# FeatherGPS6.net
KiCad netlist of a schematic drawn in EAGLE
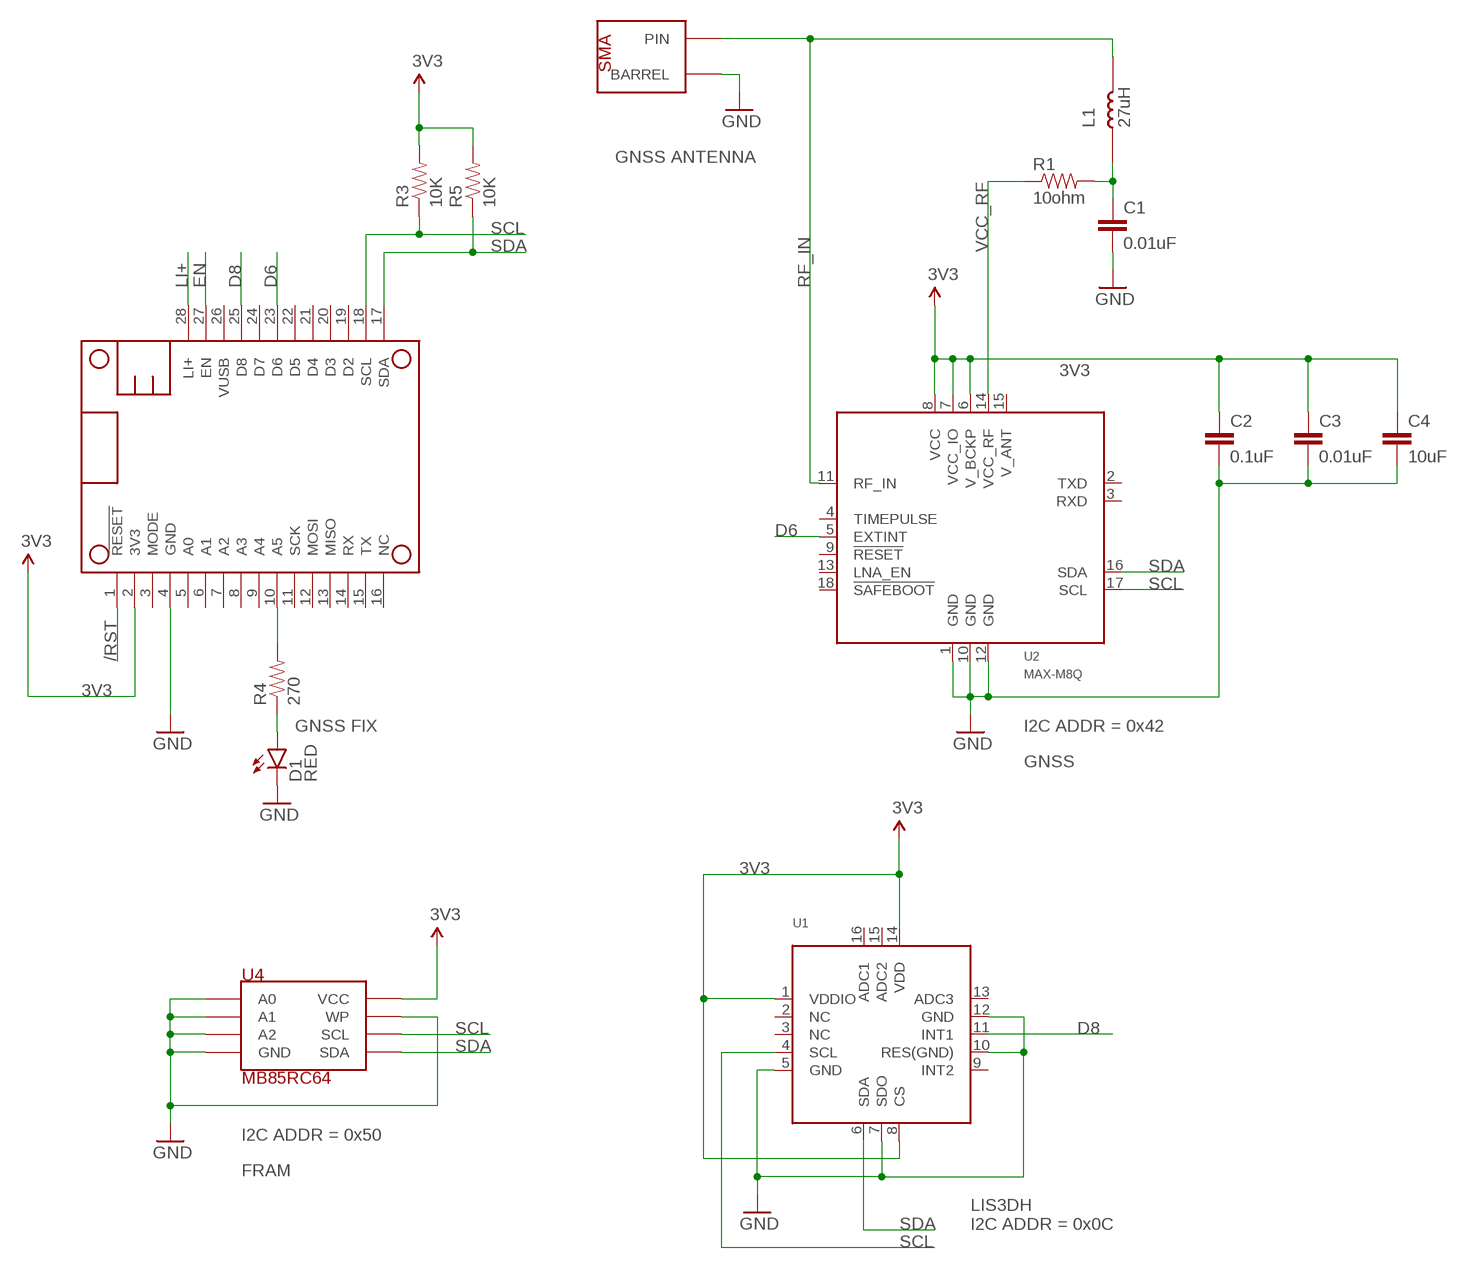
[diagram p0: schematic, sheet 1]

(export (version "E")
  (design (tool "Eeschema 10.0.6"))
  (components
    (comp (ref "C1")
      (value "0.01uF")
      (footprint "eagle-import:0603-CAP")
      (libsource (lib "eagle-import") (part "CAP-0.01UF-0603"))
    )
    (comp (ref "C2")
      (value "0.1uF")
      (footprint "eagle-import:0603-CAP")
      (libsource (lib "eagle-import") (part "CAP-0.1UF-0603"))
    )
    (comp (ref "C3")
      (value "0.01uF")
      (footprint "eagle-import:0603-CAP")
      (libsource (lib "eagle-import") (part "CAP-0.01UF-0603"))
    )
    (comp (ref "C4")
      (value "10uF")
      (footprint "eagle-import:0603-CAP")
      (libsource (lib "eagle-import") (part "CAP-10UF-0603"))
    )
    (comp (ref "D1")
      (value "RED")
      (footprint "eagle-import:LED-0603")
      (libsource (lib "eagle-import") (part "LED-RED"))
    )
    (comp (ref "J1")
      (value "SMA")
      (footprint "eagle-import:CONN-SMA")
      (libsource (lib "eagle-import") (part "CONN-SMA"))
    )
    (comp (ref "L1")
      (value "27uH")
      (footprint "eagle-import:0805")
      (libsource (lib "eagle-import") (part "INDUCTOR-27UH"))
    )
    (comp (ref "MS1")
      (value "FEATHERWING_NODIM")
      (footprint "eagle-import:FEATHERWING_NODIM")
      (libsource (lib "eagle-import") (part "FEATHERWING_NODIM"))
    )
    (comp (ref "R1")
      (value "10ohm")
      (footprint "eagle-import:0603-RES")
      (libsource (lib "eagle-import") (part "RES-10-06030603"))
    )
    (comp (ref "R3")
      (value "10K")
      (footprint "eagle-import:0603-RES")
      (libsource (lib "eagle-import") (part "RES-10K-06030603"))
    )
    (comp (ref "R4")
      (value "270")
      (footprint "eagle-import:0603-RES")
      (libsource (lib "eagle-import") (part "RES-270-0603.DEV"))
    )
    (comp (ref "R5")
      (value "10K")
      (footprint "eagle-import:0603-RES")
      (libsource (lib "eagle-import") (part "RES-10K-06030603"))
    )
    (comp (ref "U1")
      (value "LIS3DHTR")
      (footprint "eagle-import:MICROBUILDER_LGA16_3X3MM")
      (libsource (lib "eagle-import") (part "LIS3DHTR"))
    )
    (comp (ref "U2")
      (value "MAX-M8Q")
      (footprint "eagle-import:U-BLOX_MAX-M8")
      (libsource (lib "eagle-import") (part "U-BLOX_MAX-M8"))
    )
    (comp (ref "U4")
      (value "MB85RC64")
      (footprint "eagle-import:8-SOIC-MAXIM")
      (libsource (lib "eagle-import") (part "MB85RC64-FRAM"))
    )
  )
  (nets
    (net (code "1") (name "/D6") (class "Default")
      (node (ref "MS1") (pin "23") (pinfunction "D6_23") (pintype "bidirectional"))
      (node (ref "U2") (pin "5") (pinfunction "EXTINT_5") (pintype "bidirectional"))
    )
    (net (code "2") (name "/D8") (class "Default")
      (node (ref "MS1") (pin "25") (pinfunction "D8_25") (pintype "bidirectional"))
      (node (ref "U1") (pin "11") (pinfunction "INT1_11") (pintype "output"))
    )
    (net (code "3") (name "/EN") (class "Default")
      (node (ref "MS1") (pin "27") (pinfunction "EN_27") (pintype "passive"))
    )
    (net (code "4") (name "/LI+") (class "Default")
      (node (ref "MS1") (pin "28") (pinfunction "LI+_28") (pintype "power_in"))
    )
    (net (code "5") (name "/RF_IN") (class "Default")
      (node (ref "J1") (pin "PIN") (pinfunction "PIN_PIN") (pintype "passive"))
      (node (ref "L1") (pin "2") (pinfunction "P$2_2") (pintype "passive"))
      (node (ref "U2") (pin "11") (pinfunction "RF_IN_11") (pintype "bidirectional"))
    )
    (net (code "6") (name "/SCL") (class "Default")
      (node (ref "MS1") (pin "18") (pinfunction "SCL_18") (pintype "bidirectional"))
      (node (ref "R3") (pin "1") (pinfunction "1_1") (pintype "passive"))
      (node (ref "U1") (pin "4") (pinfunction "SCL_4") (pintype "bidirectional"))
      (node (ref "U2") (pin "17") (pinfunction "SCL_17") (pintype "bidirectional"))
      (node (ref "U4") (pin "6") (pinfunction "SCL_6") (pintype "input"))
    )
    (net (code "7") (name "/SDA") (class "Default")
      (node (ref "MS1") (pin "17") (pinfunction "SDA_17") (pintype "bidirectional"))
      (node (ref "R5") (pin "1") (pinfunction "1_1") (pintype "passive"))
      (node (ref "U1") (pin "6") (pinfunction "SDA_6") (pintype "bidirectional"))
      (node (ref "U2") (pin "16") (pinfunction "SDA_16") (pintype "bidirectional"))
      (node (ref "U4") (pin "5") (pinfunction "SDA_5") (pintype "bidirectional"))
    )
    (net (code "8") (name "/VCC_RF") (class "Default")
      (node (ref "R1") (pin "1") (pinfunction "1_1") (pintype "passive"))
      (node (ref "U2") (pin "14") (pinfunction "VCC_RF_14") (pintype "bidirectional"))
    )
    (net (code "9") (name "/VUSB") (class "Default")
      (node (ref "MS1") (pin "26") (pinfunction "VUSB_26") (pintype "power_in"))
    )
    (net (code "10") (name "/{slash}RST") (class "Default")
      (node (ref "MS1") (pin "1") (pinfunction "~{RESET}_1") (pintype "input"))
    )
    (net (code "11") (name "3V3") (class "Default")
      (node (ref "C2") (pin "1") (pinfunction "1_1") (pintype "passive"))
      (node (ref "C3") (pin "1") (pinfunction "1_1") (pintype "passive"))
      (node (ref "C4") (pin "1") (pinfunction "1_1") (pintype "passive"))
      (node (ref "MS1") (pin "2") (pinfunction "3V3_2") (pintype "power_in"))
      (node (ref "R3") (pin "2") (pinfunction "2_2") (pintype "passive"))
      (node (ref "R5") (pin "2") (pinfunction "2_2") (pintype "passive"))
      (node (ref "U1") (pin "1") (pinfunction "VDDIO_1") (pintype "power_in"))
      (node (ref "U1") (pin "14") (pinfunction "VDD_14") (pintype "power_in"))
      (node (ref "U1") (pin "8") (pinfunction "CS_8") (pintype "input"))
      (node (ref "U2") (pin "6") (pinfunction "V_BCKP_6") (pintype "bidirectional"))
      (node (ref "U2") (pin "7") (pinfunction "VCC_IO_7") (pintype "bidirectional"))
      (node (ref "U2") (pin "8") (pinfunction "VCC_8") (pintype "bidirectional"))
      (node (ref "U4") (pin "8") (pinfunction "VCC_8") (pintype "power_in"))
    )
    (net (code "12") (name "GND") (class "Default")
      (node (ref "C1") (pin "2") (pinfunction "2_2") (pintype "passive"))
      (node (ref "C2") (pin "2") (pinfunction "2_2") (pintype "passive"))
      (node (ref "C3") (pin "2") (pinfunction "2_2") (pintype "passive"))
      (node (ref "C4") (pin "2") (pinfunction "2_2") (pintype "passive"))
      (node (ref "D1") (pin "C") (pinfunction "C_C") (pintype "passive"))
      (node (ref "J1") (pin "2") (pinfunction "BARREL_2") (pintype "passive"))
      (node (ref "J1") (pin "3") (pinfunction "BARREL_3") (pintype "passive"))
      (node (ref "J1") (pin "4") (pinfunction "BARREL_4") (pintype "passive"))
      (node (ref "J1") (pin "5") (pinfunction "BARREL_5") (pintype "passive"))
      (node (ref "MS1") (pin "4") (pinfunction "GND_4") (pintype "power_in"))
      (node (ref "U1") (pin "10") (pinfunction "RES(GND)_10") (pintype "bidirectional"))
      (node (ref "U1") (pin "12") (pinfunction "GND_12") (pintype "power_in"))
      (node (ref "U1") (pin "5") (pinfunction "GND_5") (pintype "power_in"))
      (node (ref "U1") (pin "7") (pinfunction "SDO_7") (pintype "bidirectional"))
      (node (ref "U2") (pin "1") (pinfunction "GND_1") (pintype "bidirectional"))
      (node (ref "U2") (pin "10") (pinfunction "GND_10") (pintype "bidirectional"))
      (node (ref "U2") (pin "12") (pinfunction "GND_12") (pintype "bidirectional"))
      (node (ref "U4") (pin "1") (pinfunction "A0_1") (pintype "input"))
      (node (ref "U4") (pin "2") (pinfunction "A1_2") (pintype "input"))
      (node (ref "U4") (pin "3") (pinfunction "A2_3") (pintype "input"))
      (node (ref "U4") (pin "4") (pinfunction "GND_4") (pintype "passive"))
      (node (ref "U4") (pin "7") (pinfunction "WP_7") (pintype "input"))
    )
    (net (code "13") (name "Net-(D1-PadA)") (class "Default")
      (node (ref "D1") (pin "A") (pinfunction "A_A") (pintype "passive"))
      (node (ref "R4") (pin "1") (pinfunction "1_1") (pintype "passive"))
    )
    (net (code "14") (name "Net-(L1-P$1)") (class "Default")
      (node (ref "C1") (pin "1") (pinfunction "1_1") (pintype "passive"))
      (node (ref "L1") (pin "1") (pinfunction "P$1_1") (pintype "passive"))
      (node (ref "R1") (pin "2") (pinfunction "2_2") (pintype "passive"))
    )
    (net (code "15") (name "Net-(MS1-A5)") (class "Default")
      (node (ref "MS1") (pin "10") (pinfunction "A5_10") (pintype "bidirectional"))
      (node (ref "R4") (pin "2") (pinfunction "2_2") (pintype "passive"))
    )
    (net (code "16") (name "unconnected-(MS1-A0-Pad5)") (class "Default")
      (node (ref "MS1") (pin "5") (pinfunction "A0_5") (pintype "bidirectional"))
    )
    (net (code "17") (name "unconnected-(MS1-A1-Pad6)") (class "Default")
      (node (ref "MS1") (pin "6") (pinfunction "A1_6") (pintype "bidirectional"))
    )
    (net (code "18") (name "unconnected-(MS1-A2-Pad7)") (class "Default")
      (node (ref "MS1") (pin "7") (pinfunction "A2_7") (pintype "bidirectional"))
    )
    (net (code "19") (name "unconnected-(MS1-A3-Pad8)") (class "Default")
      (node (ref "MS1") (pin "8") (pinfunction "A3_8") (pintype "bidirectional"))
    )
    (net (code "20") (name "unconnected-(MS1-A4-Pad9)") (class "Default")
      (node (ref "MS1") (pin "9") (pinfunction "A4_9") (pintype "bidirectional"))
    )
    (net (code "21") (name "unconnected-(MS1-D2-Pad19)") (class "Default")
      (node (ref "MS1") (pin "19") (pinfunction "D2_19") (pintype "bidirectional"))
    )
    (net (code "22") (name "unconnected-(MS1-D3-Pad20)") (class "Default")
      (node (ref "MS1") (pin "20") (pinfunction "D3_20") (pintype "bidirectional"))
    )
    (net (code "23") (name "unconnected-(MS1-D4-Pad21)") (class "Default")
      (node (ref "MS1") (pin "21") (pinfunction "D4_21") (pintype "bidirectional"))
    )
    (net (code "24") (name "unconnected-(MS1-D5-Pad22)") (class "Default")
      (node (ref "MS1") (pin "22") (pinfunction "D5_22") (pintype "bidirectional"))
    )
    (net (code "25") (name "unconnected-(MS1-D7-Pad24)") (class "Default")
      (node (ref "MS1") (pin "24") (pinfunction "D7_24") (pintype "bidirectional"))
    )
    (net (code "26") (name "unconnected-(MS1-MISO-Pad13)") (class "Default")
      (node (ref "MS1") (pin "13") (pinfunction "MISO_13") (pintype "bidirectional"))
    )
    (net (code "27") (name "unconnected-(MS1-MODE-Pad3)") (class "Default")
      (node (ref "MS1") (pin "3") (pinfunction "MODE_3") (pintype "passive"))
    )
    (net (code "28") (name "unconnected-(MS1-MOSI-Pad12)") (class "Default")
      (node (ref "MS1") (pin "12") (pinfunction "MOSI_12") (pintype "bidirectional"))
    )
    (net (code "29") (name "unconnected-(MS1-NC-Pad16)") (class "Default")
      (node (ref "MS1") (pin "16") (pinfunction "NC_16") (pintype "passive"))
    )
    (net (code "30") (name "unconnected-(MS1-RX-Pad14)") (class "Default")
      (node (ref "MS1") (pin "14") (pinfunction "RX_14") (pintype "bidirectional"))
    )
    (net (code "31") (name "unconnected-(MS1-SCK-Pad11)") (class "Default")
      (node (ref "MS1") (pin "11") (pinfunction "SCK_11") (pintype "bidirectional"))
    )
    (net (code "32") (name "unconnected-(MS1-TX-Pad15)") (class "Default")
      (node (ref "MS1") (pin "15") (pinfunction "TX_15") (pintype "bidirectional"))
    )
    (net (code "33") (name "unconnected-(U1-ADC1-Pad16)") (class "Default")
      (node (ref "U1") (pin "16") (pinfunction "ADC1_16") (pintype "input"))
    )
    (net (code "34") (name "unconnected-(U1-ADC2-Pad15)") (class "Default")
      (node (ref "U1") (pin "15") (pinfunction "ADC2_15") (pintype "input"))
    )
    (net (code "35") (name "unconnected-(U1-ADC3-Pad13)") (class "Default")
      (node (ref "U1") (pin "13") (pinfunction "ADC3_13") (pintype "input"))
    )
    (net (code "36") (name "unconnected-(U1-INT2-Pad9)") (class "Default")
      (node (ref "U1") (pin "9") (pinfunction "INT2_9") (pintype "output"))
    )
    (net (code "37") (name "unconnected-(U1-NC-Pad2)") (class "Default")
      (node (ref "U1") (pin "2") (pinfunction "NC_2") (pintype "no_connect"))
    )
    (net (code "38") (name "unconnected-(U1-NC-Pad3)") (class "Default")
      (node (ref "U1") (pin "3") (pinfunction "NC_3") (pintype "no_connect"))
    )
    (net (code "39") (name "unconnected-(U2-LNA_EN-Pad13)") (class "Default")
      (node (ref "U2") (pin "13") (pinfunction "LNA_EN_13") (pintype "bidirectional"))
    )
    (net (code "40") (name "unconnected-(U2-RXD-Pad3)") (class "Default")
      (node (ref "U2") (pin "3") (pinfunction "RXD_3") (pintype "bidirectional"))
    )
    (net (code "41") (name "unconnected-(U2-TIMEPULSE-Pad4)") (class "Default")
      (node (ref "U2") (pin "4") (pinfunction "TIMEPULSE_4") (pintype "bidirectional"))
    )
    (net (code "42") (name "unconnected-(U2-TXD-Pad2)") (class "Default")
      (node (ref "U2") (pin "2") (pinfunction "TXD_2") (pintype "bidirectional"))
    )
    (net (code "43") (name "unconnected-(U2-V_ANT-Pad15)") (class "Default")
      (node (ref "U2") (pin "15") (pinfunction "V_ANT_15") (pintype "bidirectional"))
    )
    (net (code "44") (name "unconnected-(U2-~{RESET}-Pad9)") (class "Default")
      (node (ref "U2") (pin "9") (pinfunction "~{RESET}_9") (pintype "bidirectional"))
    )
    (net (code "45") (name "unconnected-(U2-~{SAFEBOOT}-Pad18)") (class "Default")
      (node (ref "U2") (pin "18") (pinfunction "~{SAFEBOOT}_18") (pintype "bidirectional"))
    )
  )
)
